# SCH_W-F-FC-HX2X.net
KiCad netlist of a schematic drawn in Altium Designer
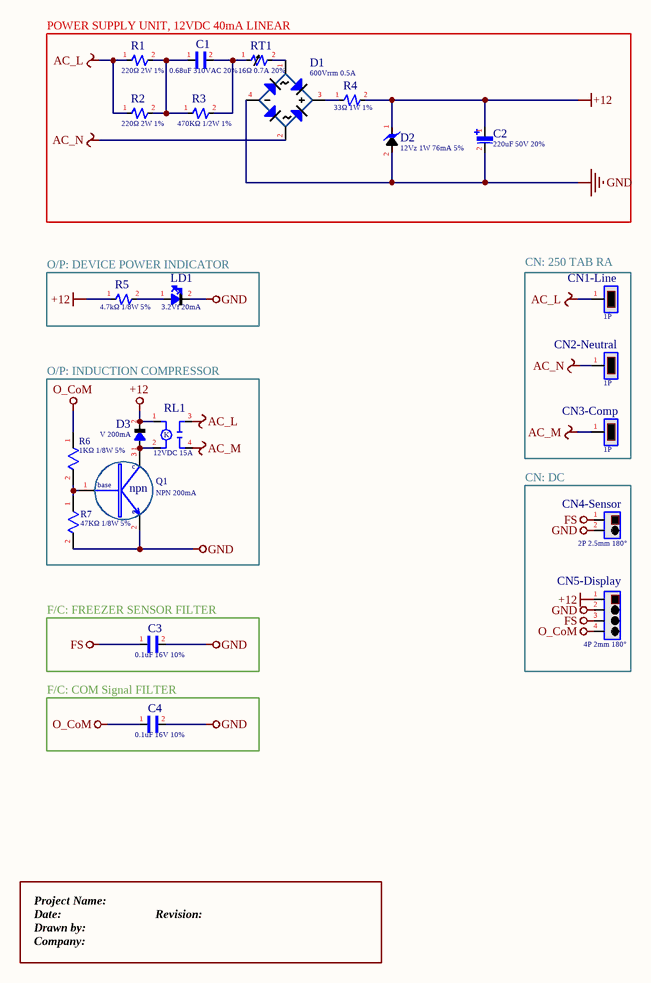
[diagram p0: SCH_W-F-FC-HX2X.SchDoc]

(export (version "E")
  (design (tool "Eeschema 10.0.6"))
  (components
    (comp (ref "C1")
      (value "0.68uF 310VAC 20%")
      (footprint "C_X2_18X10X15.8_P15")
      (description "684K310V, P=15 18*9.5*15.5, Climate-category: 40/110/56")
      (libsource (lib "RBM_ALTIUM_SCH_LIBRARY") (part "Capacitor{gt}{gt} Non-Polar"))
    )
    (comp (ref "C2")
      (value "220uF 50V 20%")
      (footprint "C_Radial_Ø8*11mm_P3.5")
      (description "Aluminum Electrolytic Capacitor, Through Hole, ØDxL=8*11mm Pitch=3.5mm")
      (libsource (lib "RBM_ALTIUM_SCH_LIBRARY") (part "Capacitor{gt}{gt} Polar"))
    )
    (comp (ref "C3")
      (value "0.1uF 16V 10%")
      (footprint "C_0805")
      (description "Multilayer Ceramic Capacitors, SMD 0805")
      (libsource (lib "RBM_ALTIUM_SCH_LIBRARY") (part "Capacitor{gt}{gt} Non-Polar"))
    )
    (comp (ref "C4")
      (value "0.1uF 16V 10%")
      (footprint "C_0805")
      (description "Multilayer Ceramic Capacitors, SMD 0805")
      (libsource (lib "RBM_ALTIUM_SCH_LIBRARY") (part "Capacitor{gt}{gt} Non-Polar"))
    )
    (comp (ref "CN1-Line")
      (value "1P")
      (footprint "CN_Tab Terminal 250 series (Right Angle)")
      (description "6.3mm PCB Tab Terminal (Right Angle)")
      (libsource (lib "RBM_ALTIUM_SCH_LIBRARY") (part "Connector{gt}{gt} 1Pin"))
    )
    (comp (ref "CN2-Neutral")
      (value "1P")
      (footprint "CN_Tab Terminal 250 series (Right Angle)")
      (description "6.3mm PCB Tab Terminal (Right Angle)")
      (libsource (lib "RBM_ALTIUM_SCH_LIBRARY") (part "Connector{gt}{gt} 1Pin"))
    )
    (comp (ref "CN3-Comp")
      (value "1P")
      (footprint "CN_Tab Terminal 250 series (Right Angle)")
      (description "6.3mm PCB Tab Terminal (Right Angle)")
      (libsource (lib "RBM_ALTIUM_SCH_LIBRARY") (part "Connector{gt}{gt} 1Pin"))
    )
    (comp (ref "CN4-Sensor")
      (value "2P 2.5mm 180°")
      (footprint "CN_B2B-XH-A_RED")
      (description "A2512WV-XP, 2Pins, 2.5mmPitch, 180° Wafer, RED, Through Hole")
      (libsource (lib "RBM_ALTIUM_SCH_LIBRARY") (part "Connector{gt}{gt} 2Pins"))
    )
    (comp (ref "CN5-Display")
      (value "4P 2mm 180°")
      (footprint "CN_4P_A2001WV-XP-180DEG")
      (description "A2001WV-XP, 4Pins, 2mmPitch, 180° Wafer, White, , Through Hole")
      (libsource (lib "RBM_ALTIUM_SCH_LIBRARY") (part "Connector{gt}{gt} 4Pins"))
    )
    (comp (ref "D1")
      (value "600Vrrm 0.5A")
      (footprint "D_SMD_MB6S")
      (description "MB6S, SOIC, ON-SEMICONDUCTOR")
      (libsource (lib "RBM_ALTIUM_SCH_LIBRARY") (part "Diode{gt}{gt} Bridge Rectifier"))
    )
    (comp (ref "D2")
      (value "12Vz 1W 76mA 5%")
      (footprint "D_SMD_LL-41")
      (description "ZM4742, MELF SILICON PLANAR POWER ZENER DIODES, LL-41")
      (libsource (lib "RBM_ALTIUM_SCH_LIBRARY") (part "Diode{gt}{gt} Zener"))
    )
    (comp (ref "D3")
      (value "V 200mA")
      (footprint "D_SOT-23-3_200mA")
      (description "BAS19, SOT-23-3")
      (libsource (lib "RBM_ALTIUM_SCH_LIBRARY") (part "Diode{gt}{gt} General Purpose"))
    )
    (comp (ref "LD1")
      (value "3.2Vf 20mA")
      (footprint "LED_3x5_P2.5")
      (description "RED, Through hole, ØDxH=3x5mm Pitch=2.5mm")
      (libsource (lib "RBM_ALTIUM_SCH_LIBRARY") (part "LED{gt}{gt} General Purpose"))
    )
    (comp (ref "Q1")
      (value "NPN 200mA")
      (footprint "Q_SOT-23-3_NPN_BC847")
      (description "BC847, SOT-23-3")
      (libsource (lib "RBM_SCH-Lib_16-Apr-19") (part "BJT_npn"))
    )
    (comp (ref "R1")
      (value "220Ω 2W 1%")
      (footprint "R_Axial_P15")
      (description "Metal Oxide Film Resistor, Through Hole Axial, L=12, øD=5, H=28, ød=0.6, Flame Proof")
      (libsource (lib "RBM_ALTIUM_SCH_LIBRARY") (part "Resistor{gt}{gt} General Purpose"))
    )
    (comp (ref "R2")
      (value "220Ω 2W 1%")
      (footprint "R_Axial_P15")
      (description "Metal Oxide Film Resistor, Through Hole Axial, L=12, øD=5, H=28, ød=0.6, Flame Proof")
      (libsource (lib "RBM_ALTIUM_SCH_LIBRARY") (part "Resistor{gt}{gt} General Purpose"))
    )
    (comp (ref "R3")
      (value "470KΩ 1/2W 1%")
      (footprint "R_Axial_P10")
      (description "Metal Oxide Film Resistor, Through Hole Axial, L=7, øD=2.5, H=28, ød=0.48, Flame Proof")
      (libsource (lib "RBM_ALTIUM_SCH_LIBRARY") (part "Resistor{gt}{gt} General Purpose"))
    )
    (comp (ref "R4")
      (value "33Ω 1W 1%")
      (footprint "R_Axial_P15")
      (description "Metal Oxide Film Resistor, Through Hole Axial, L=10, øD=4, H=28, ød=0.5, Flame Proof")
      (libsource (lib "RBM_ALTIUM_SCH_LIBRARY") (part "Resistor{gt}{gt} General Purpose"))
    )
    (comp (ref "R5")
      (value "4.7kΩ 1/8W 5%")
      (footprint "R_0805")
      (description "Chip-Resistor, SMD 0805, , RoHS")
      (libsource (lib "RBM_ALTIUM_SCH_LIBRARY") (part "Resistor{gt}{gt} General Purpose"))
    )
    (comp (ref "R6")
      (value "1KΩ 1/8W 5%")
      (footprint "R_0805")
      (description "Chip-Resistor, SMD 0805, , RoHS")
      (libsource (lib "RBM_SCH-Lib_16-Apr-19") (part "Resistor"))
    )
    (comp (ref "R7")
      (value "47KΩ 1/8W 5%")
      (footprint "R_0805")
      (description "Chip-Resistor, SMD 0805, , RoHS")
      (libsource (lib "RBM_SCH-Lib_16-Apr-19") (part "Resistor"))
    )
    (comp (ref "RL1")
      (value "12VDC 15A")
      (footprint "RL_SPST_15ARelay_AZ943-1AH-12DE")
      (description "Zettler AZ943–1CH–12DE")
      (libsource (lib "RBM_ALTIUM_SCH_LIBRARY") (part "Relay{gt}{gt} SPST"))
    )
    (comp (ref "RT1")
      (value "16Ω 0.7A 20%")
      (footprint "NTC_5mmPitch")
      (description "16D-7, NTC, Pitch 5mm")
      (libsource (lib "RBM_ALTIUM_SCH_LIBRARY") (part "Thermistor{gt}{gt} NTC"))
    )
  )
  (nets
    (net (code "1") (name "+12") (class "Default")
      (node (ref "C2") (pin "1") (pinfunction "1_1") (pintype "passive"))
      (node (ref "CN5-Display") (pin "1") (pinfunction "1_1") (pintype "passive"))
      (node (ref "D2") (pin "1") (pinfunction "A_1") (pintype "passive"))
      (node (ref "D3") (pin "2") (pinfunction "K_2") (pintype "passive"))
      (node (ref "R4") (pin "2") (pinfunction "2_2") (pintype "passive"))
      (node (ref "R5") (pin "1") (pinfunction "1_1") (pintype "passive"))
      (node (ref "RL1") (pin "1") (pinfunction "1_1") (pintype "passive"))
    )
    (net (code "2") (name "AC_L") (class "Default")
      (node (ref "CN1-Line") (pin "1") (pinfunction "1_1") (pintype "passive"))
      (node (ref "R1") (pin "1") (pinfunction "1_1") (pintype "passive"))
      (node (ref "R2") (pin "1") (pinfunction "1_1") (pintype "passive"))
      (node (ref "RL1") (pin "3") (pinfunction "3_3") (pintype "passive"))
    )
    (net (code "3") (name "AC_M") (class "Default")
      (node (ref "CN3-Comp") (pin "1") (pinfunction "1_1") (pintype "passive"))
      (node (ref "RL1") (pin "4") (pinfunction "4_4") (pintype "passive"))
    )
    (net (code "4") (name "AC_N") (class "Default")
      (node (ref "CN2-Neutral") (pin "1") (pinfunction "1_1") (pintype "passive"))
      (node (ref "D1") (pin "2") (pinfunction "AC_2") (pintype "passive"))
    )
    (net (code "5") (name "FS") (class "Default")
      (node (ref "C3") (pin "1") (pinfunction "1_1") (pintype "passive"))
      (node (ref "CN4-Sensor") (pin "1") (pinfunction "1_1") (pintype "passive"))
      (node (ref "CN5-Display") (pin "3") (pinfunction "3_3") (pintype "passive"))
    )
    (net (code "6") (name "GND") (class "Default")
      (node (ref "C2") (pin "2") (pinfunction "2_2") (pintype "passive"))
      (node (ref "C3") (pin "2") (pinfunction "2_2") (pintype "passive"))
      (node (ref "C4") (pin "2") (pinfunction "2_2") (pintype "passive"))
      (node (ref "CN4-Sensor") (pin "2") (pinfunction "2_2") (pintype "passive"))
      (node (ref "CN5-Display") (pin "2") (pinfunction "2_2") (pintype "passive"))
      (node (ref "D1") (pin "4") (pinfunction "vss_4") (pintype "passive"))
      (node (ref "D2") (pin "2") (pinfunction "K_2") (pintype "passive"))
      (node (ref "LD1") (pin "2") (pinfunction "vss_2") (pintype "passive"))
      (node (ref "Q1") (pin "2") (pinfunction "Emitter_2") (pintype "passive"))
      (node (ref "R7") (pin "2") (pinfunction "2_2") (pintype "passive"))
    )
    (net (code "7") (name "Net-(C1-Pad1)") (class "Default")
      (node (ref "C1") (pin "1") (pinfunction "1_1") (pintype "passive"))
      (node (ref "R1") (pin "2") (pinfunction "2_2") (pintype "passive"))
      (node (ref "R2") (pin "2") (pinfunction "2_2") (pintype "passive"))
      (node (ref "R3") (pin "1") (pinfunction "1_1") (pintype "passive"))
    )
    (net (code "8") (name "Net-(C1-Pad2)") (class "Default")
      (node (ref "C1") (pin "2") (pinfunction "2_2") (pintype "passive"))
      (node (ref "R3") (pin "2") (pinfunction "2_2") (pintype "passive"))
      (node (ref "RT1") (pin "1") (pinfunction "1_1") (pintype "passive"))
    )
    (net (code "9") (name "Net-(D1-AC-Pad1)") (class "Default")
      (node (ref "D1") (pin "1") (pinfunction "AC_1") (pintype "passive"))
      (node (ref "RT1") (pin "2") (pinfunction "2_2") (pintype "passive"))
    )
    (net (code "10") (name "Net-(D1-VCC)") (class "Default")
      (node (ref "D1") (pin "3") (pinfunction "VCC_3") (pintype "passive"))
      (node (ref "R4") (pin "1") (pinfunction "1_1") (pintype "passive"))
    )
    (net (code "11") (name "Net-(D3-A)") (class "Default")
      (node (ref "D3") (pin "1") (pinfunction "A_1") (pintype "passive"))
      (node (ref "Q1") (pin "3") (pinfunction "Collector_3") (pintype "passive"))
      (node (ref "RL1") (pin "2") (pinfunction "2_2") (pintype "passive"))
    )
    (net (code "12") (name "Net-(LD1-vdd)") (class "Default")
      (node (ref "LD1") (pin "1") (pinfunction "vdd_1") (pintype "passive"))
      (node (ref "R5") (pin "2") (pinfunction "2_2") (pintype "passive"))
    )
    (net (code "13") (name "Net-(Q1-Base)") (class "Default")
      (node (ref "Q1") (pin "1") (pinfunction "Base_1") (pintype "passive"))
      (node (ref "R6") (pin "2") (pinfunction "2_2") (pintype "passive"))
      (node (ref "R7") (pin "1") (pinfunction "1_1") (pintype "passive"))
    )
    (net (code "14") (name "O_CoM") (class "Default")
      (node (ref "C4") (pin "1") (pinfunction "1_1") (pintype "passive"))
      (node (ref "CN5-Display") (pin "4") (pinfunction "4_4") (pintype "passive"))
      (node (ref "R6") (pin "1") (pinfunction "1_1") (pintype "passive"))
    )
  )
)
